# ST_LINK_V3EC.net
KiCad netlist of a schematic drawn in Altium Designer
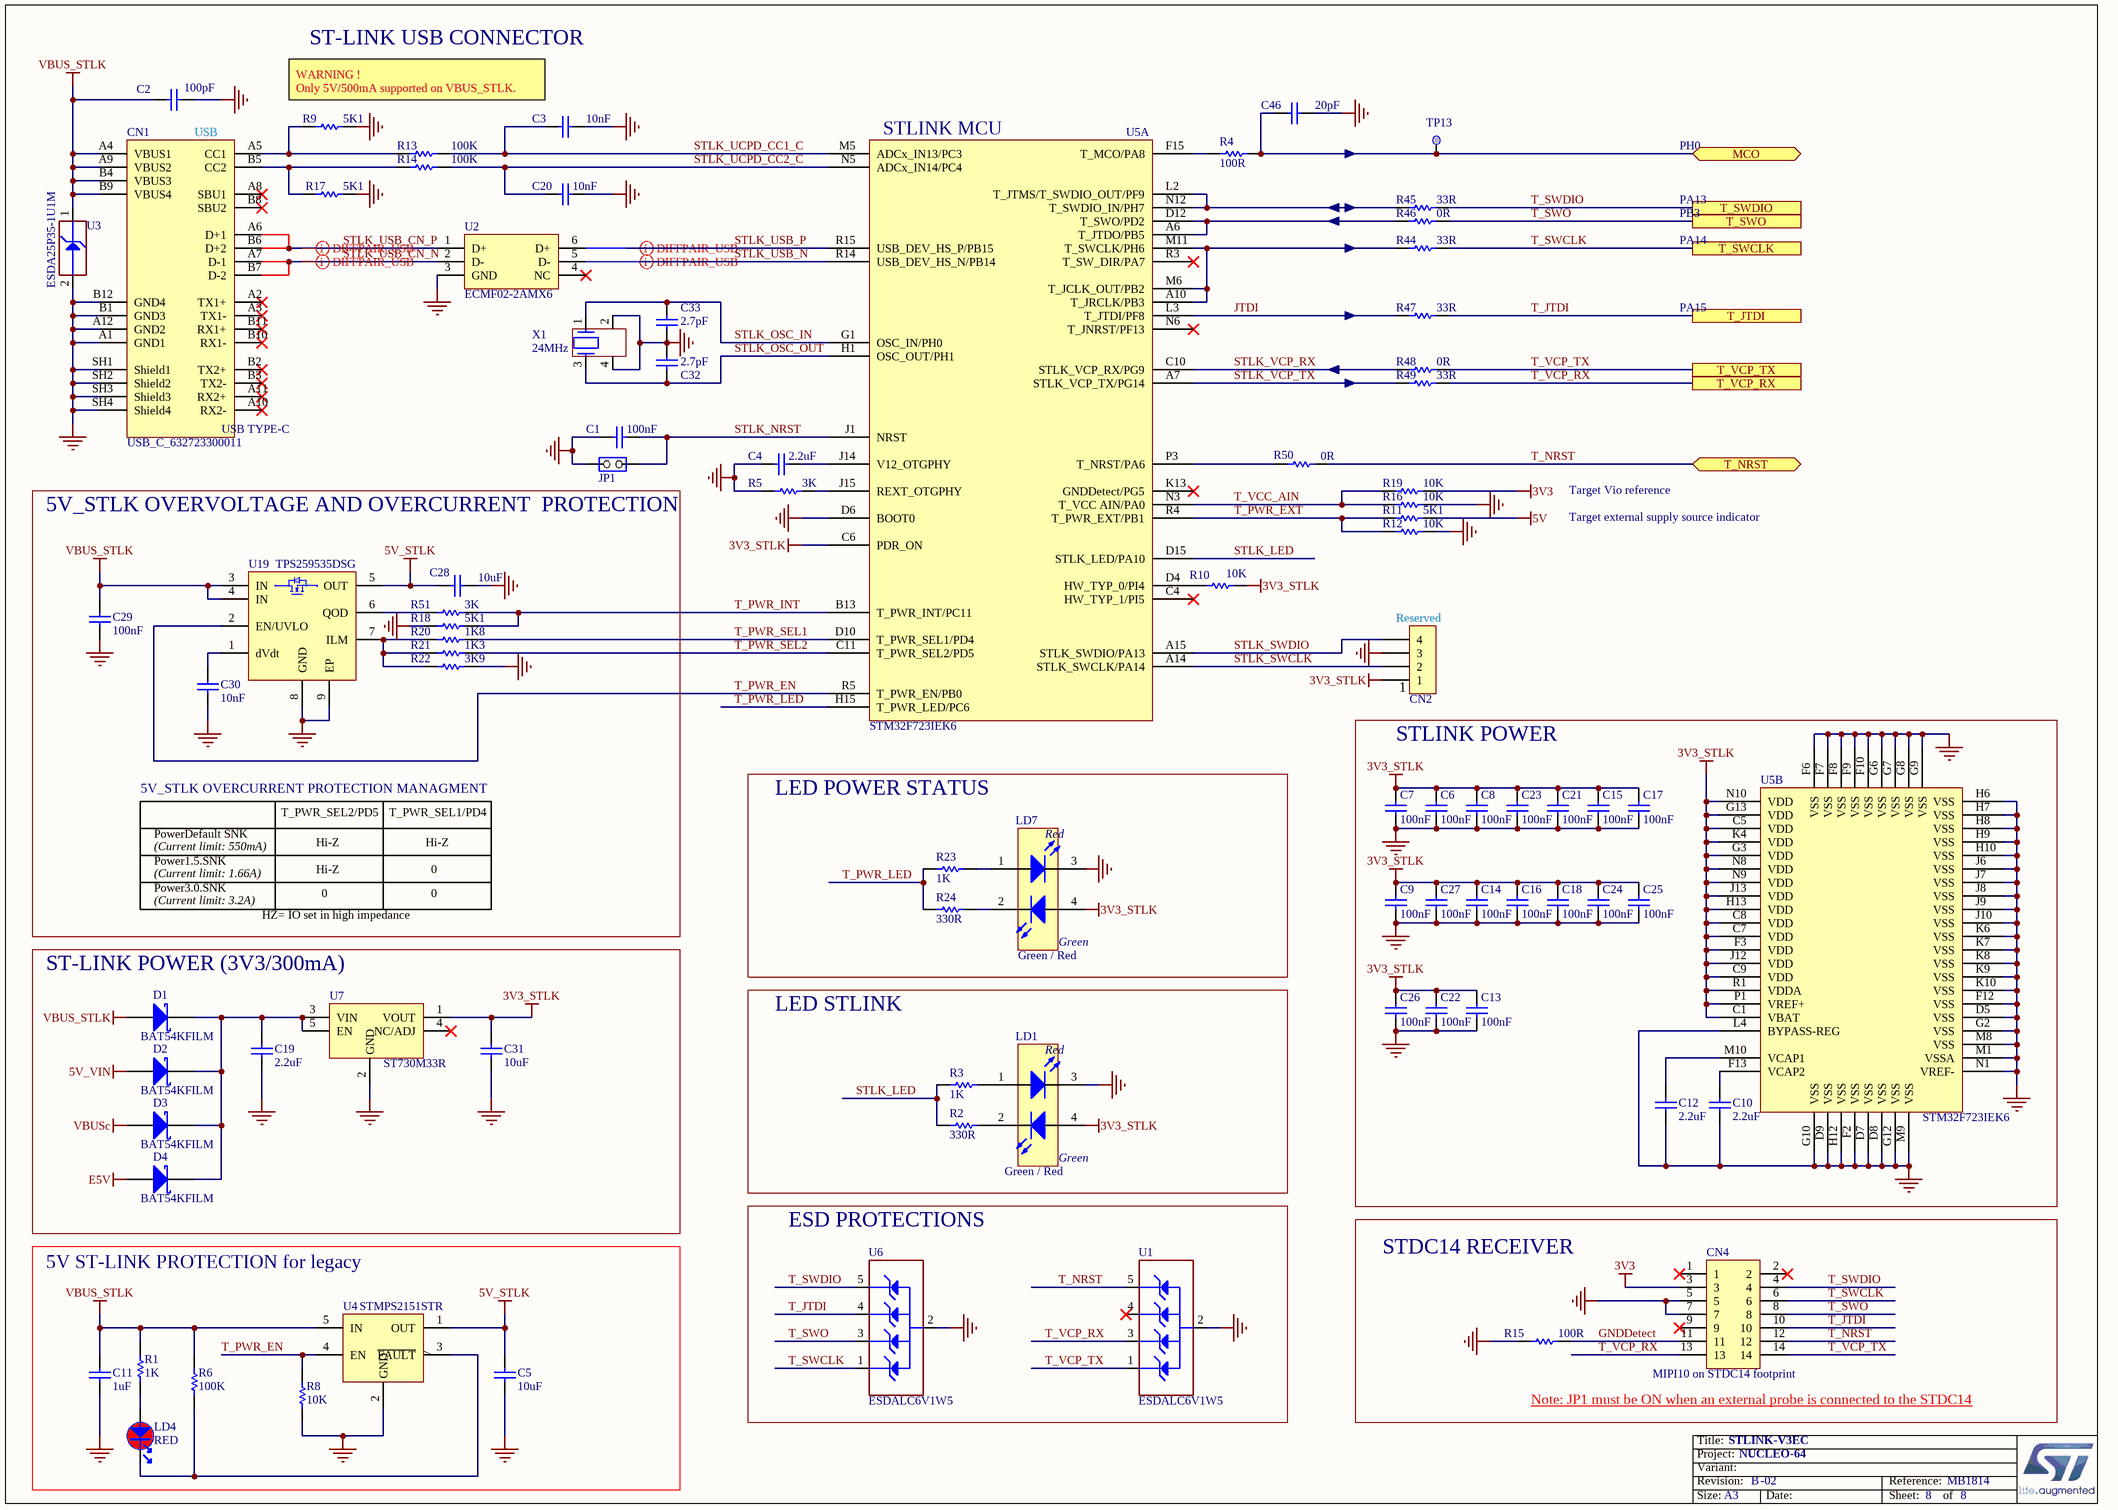
[diagram p0: ST_LINK_V3EC.SchDoc]

(export (version "E")
  (design (tool "Eeschema 10.0.6"))
  (components
    (comp (ref "C1")
      (value "100nF")
      (footprint "C0402")
      (description "Capacitor, MLCC, 100nF, 16V, X7R, 10%, 0402, T=0.5mm")
      (fields
        (field (name "INTERNAL_PART_NUMBER") "MCD-00006")
        (field (name "MANUFACTURER_PART_NUMBER") "CC0402KRX7R7BB104")
        (field (name "PROVIDED_BY") "SUBCO")
      )
      (libsource (lib "MCD_PARTS_database") (part "Capacitor"))
    )
    (comp (ref "C2")
      (value "100pF")
      (footprint "C0402")
      (description "Capacitor, MLCC, 100pF, 50V, NPO, +/-5%, 0402, T=0.5mm")
      (fields (field (name "INTERNAL_PART_NUMBER") "MCD-00205") (field (name "MANUFACTURER") "YAGEO"))
      (libsource (lib "MCD_PARTS_database") (part "Capacitor"))
    )
    (comp (ref "C3")
      (value "10nF")
      (footprint "C0402")
      (description "Capacitor, MLCC, 10nF, 50V, X7R, +/-10%, 0402, T=0.5mm")
      (fields (field (name "INTERNAL_PART_NUMBER") "MCD-02198") (field (name "MANUFACTURER") "YAGEO"))
      (libsource (lib "MCD_PARTS_database") (part "Capacitor"))
    )
    (comp (ref "C4")
      (value "2.2uF")
      (footprint "C0402")
      (description "Capacitor, MLCC, 2.2uF, 6.3V, X5R, +/-10%, 0402, T=0.5mm")
      (fields (field (name "INTERNAL_PART_NUMBER") "MCD-02606") (field (name "MANUFACTURER") "YAGEO"))
      (libsource (lib "MCD_PARTS_database") (part "Capacitor"))
    )
    (comp (ref "C5")
      (value "10uF")
      (footprint "C0603")
      (description "Capacitor, MLCC, 10uF, 10V, X5R, +/-10%, 0603, T=0.8mm")
      (fields (field (name "INTERNAL_PART_NUMBER") "MCD-00099") (field (name "MANUFACTURER") "MURATA"))
      (libsource (lib "MCD_PARTS_database") (part "Capacitor"))
    )
    (comp (ref "C6")
      (value "100nF")
      (footprint "C0402")
      (description "Capacitor, MLCC, 100nF, 16V, X7R, 10%, 0402, T=0.5mm")
      (fields
        (field (name "INTERNAL_PART_NUMBER") "MCD-00006")
        (field (name "MANUFACTURER_PART_NUMBER") "CC0402KRX7R7BB104")
        (field (name "PROVIDED_BY") "SUBCO")
      )
      (libsource (lib "MCD_PARTS_database") (part "Capacitor"))
    )
    (comp (ref "C7")
      (value "100nF")
      (footprint "C0402")
      (description "Capacitor, MLCC, 100nF, 16V, X7R, 10%, 0402, T=0.5mm")
      (fields
        (field (name "INTERNAL_PART_NUMBER") "MCD-00006")
        (field (name "MANUFACTURER_PART_NUMBER") "CC0402KRX7R7BB104")
        (field (name "PROVIDED_BY") "SUBCO")
      )
      (libsource (lib "MCD_PARTS_database") (part "Capacitor"))
    )
    (comp (ref "C8")
      (value "100nF")
      (footprint "C0402")
      (description "Capacitor, MLCC, 100nF, 16V, X7R, 10%, 0402, T=0.5mm")
      (fields
        (field (name "INTERNAL_PART_NUMBER") "MCD-00006")
        (field (name "MANUFACTURER_PART_NUMBER") "CC0402KRX7R7BB104")
        (field (name "PROVIDED_BY") "SUBCO")
      )
      (libsource (lib "MCD_PARTS_database") (part "Capacitor"))
    )
    (comp (ref "C9")
      (value "100nF")
      (footprint "C0402")
      (description "Capacitor, MLCC, 100nF, 16V, X7R, 10%, 0402, T=0.5mm")
      (fields
        (field (name "INTERNAL_PART_NUMBER") "MCD-00006")
        (field (name "MANUFACTURER_PART_NUMBER") "CC0402KRX7R7BB104")
        (field (name "PROVIDED_BY") "SUBCO")
      )
      (libsource (lib "MCD_PARTS_database") (part "Capacitor"))
    )
    (comp (ref "C10")
      (value "2.2uF")
      (footprint "C0402")
      (description "Capacitor, MLCC, 2.2uF, 6.3V, X5R, +/-10%, 0402, T=0.5mm")
      (fields (field (name "INTERNAL_PART_NUMBER") "MCD-02606") (field (name "MANUFACTURER") "YAGEO"))
      (libsource (lib "MCD_PARTS_database") (part "Capacitor"))
    )
    (comp (ref "C11")
      (value "1uF")
      (footprint "C0603")
      (description "Capacitor, MLCC, 1uF, 16V, X5R, 10%, 0603, T=0,8mm")
      (fields
        (field (name "INTERNAL_PART_NUMBER") "MCD-00010")
        (field (name "MANUFACTURER_PART_NUMBER") "CC0603KRX5R7BB105")
        (field (name "PROVIDED_BY") "SUBCO")
      )
      (libsource (lib "MCD_PARTS_database") (part "Capacitor"))
    )
    (comp (ref "C12")
      (value "2.2uF")
      (footprint "C0402")
      (description "Capacitor, MLCC, 2.2uF, 6.3V, X5R, +/-10%, 0402, T=0.5mm")
      (fields (field (name "INTERNAL_PART_NUMBER") "MCD-02606") (field (name "MANUFACTURER") "YAGEO"))
      (libsource (lib "MCD_PARTS_database") (part "Capacitor"))
    )
    (comp (ref "C13")
      (value "100nF")
      (footprint "C0402")
      (description "Capacitor, MLCC, 100nF, 16V, X7R, 10%, 0402, T=0.5mm")
      (fields
        (field (name "INTERNAL_PART_NUMBER") "MCD-00006")
        (field (name "MANUFACTURER_PART_NUMBER") "CC0402KRX7R7BB104")
        (field (name "PROVIDED_BY") "SUBCO")
      )
      (libsource (lib "MCD_PARTS_database") (part "Capacitor"))
    )
    (comp (ref "C14")
      (value "100nF")
      (footprint "C0402")
      (description "Capacitor, MLCC, 100nF, 16V, X7R, 10%, 0402, T=0.5mm")
      (fields
        (field (name "INTERNAL_PART_NUMBER") "MCD-00006")
        (field (name "MANUFACTURER_PART_NUMBER") "CC0402KRX7R7BB104")
        (field (name "PROVIDED_BY") "SUBCO")
      )
      (libsource (lib "MCD_PARTS_database") (part "Capacitor"))
    )
    (comp (ref "C15")
      (value "100nF")
      (footprint "C0402")
      (description "Capacitor, MLCC, 100nF, 16V, X7R, 10%, 0402, T=0.5mm")
      (fields
        (field (name "INTERNAL_PART_NUMBER") "MCD-00006")
        (field (name "MANUFACTURER_PART_NUMBER") "CC0402KRX7R7BB104")
        (field (name "PROVIDED_BY") "SUBCO")
      )
      (libsource (lib "MCD_PARTS_database") (part "Capacitor"))
    )
    (comp (ref "C16")
      (value "100nF")
      (footprint "C0402")
      (description "Capacitor, MLCC, 100nF, 16V, X7R, 10%, 0402, T=0.5mm")
      (fields
        (field (name "INTERNAL_PART_NUMBER") "MCD-00006")
        (field (name "MANUFACTURER_PART_NUMBER") "CC0402KRX7R7BB104")
        (field (name "PROVIDED_BY") "SUBCO")
      )
      (libsource (lib "MCD_PARTS_database") (part "Capacitor"))
    )
    (comp (ref "C17")
      (value "100nF")
      (footprint "C0402")
      (description "Capacitor, MLCC, 100nF, 16V, X7R, 10%, 0402, T=0.5mm")
      (fields
        (field (name "INTERNAL_PART_NUMBER") "MCD-00006")
        (field (name "MANUFACTURER_PART_NUMBER") "CC0402KRX7R7BB104")
        (field (name "PROVIDED_BY") "SUBCO")
      )
      (libsource (lib "MCD_PARTS_database") (part "Capacitor"))
    )
    (comp (ref "C18")
      (value "100nF")
      (footprint "C0402")
      (description "Capacitor, MLCC, 100nF, 16V, X7R, 10%, 0402, T=0.5mm")
      (fields
        (field (name "INTERNAL_PART_NUMBER") "MCD-00006")
        (field (name "MANUFACTURER_PART_NUMBER") "CC0402KRX7R7BB104")
        (field (name "PROVIDED_BY") "SUBCO")
      )
      (libsource (lib "MCD_PARTS_database") (part "Capacitor"))
    )
    (comp (ref "C19")
      (value "2.2uF")
      (footprint "C0805")
      (description "Capacitor, MLCC, 2.2uF, 25V, X7R, +/-10%, 0805, T=1,25mm")
      (fields
        (field (name "INTERNAL_PART_NUMBER") "MCD-02372")
        (field (name "MANUFACTURER_PART_NUMBER") "GRM21BR71E225KE11L")
        (field (name "PROVIDED_BY") "SUBCO")
      )
      (libsource (lib "MCD_PARTS_database") (part "Capacitor"))
    )
    (comp (ref "C20")
      (value "10nF")
      (footprint "C0402")
      (description "Capacitor, MLCC, 10nF, 50V, X7R, +/-10%, 0402, T=0.5mm")
      (fields (field (name "INTERNAL_PART_NUMBER") "MCD-02198") (field (name "MANUFACTURER") "YAGEO"))
      (libsource (lib "MCD_PARTS_database") (part "Capacitor"))
    )
    (comp (ref "C21")
      (value "100nF")
      (footprint "C0402")
      (description "Capacitor, MLCC, 100nF, 16V, X7R, 10%, 0402, T=0.5mm")
      (fields
        (field (name "INTERNAL_PART_NUMBER") "MCD-00006")
        (field (name "MANUFACTURER_PART_NUMBER") "CC0402KRX7R7BB104")
        (field (name "PROVIDED_BY") "SUBCO")
      )
      (libsource (lib "MCD_PARTS_database") (part "Capacitor"))
    )
    (comp (ref "C22")
      (value "100nF")
      (footprint "C0402")
      (description "Capacitor, MLCC, 100nF, 16V, X7R, 10%, 0402, T=0.5mm")
      (fields
        (field (name "INTERNAL_PART_NUMBER") "MCD-00006")
        (field (name "MANUFACTURER_PART_NUMBER") "CC0402KRX7R7BB104")
        (field (name "PROVIDED_BY") "SUBCO")
      )
      (libsource (lib "MCD_PARTS_database") (part "Capacitor"))
    )
    (comp (ref "C23")
      (value "100nF")
      (footprint "C0402")
      (description "Capacitor, MLCC, 100nF, 16V, X7R, 10%, 0402, T=0.5mm")
      (fields
        (field (name "INTERNAL_PART_NUMBER") "MCD-00006")
        (field (name "MANUFACTURER_PART_NUMBER") "CC0402KRX7R7BB104")
        (field (name "PROVIDED_BY") "SUBCO")
      )
      (libsource (lib "MCD_PARTS_database") (part "Capacitor"))
    )
    (comp (ref "C24")
      (value "100nF")
      (footprint "C0402")
      (description "Capacitor, MLCC, 100nF, 16V, X7R, 10%, 0402, T=0.5mm")
      (fields
        (field (name "INTERNAL_PART_NUMBER") "MCD-00006")
        (field (name "MANUFACTURER_PART_NUMBER") "CC0402KRX7R7BB104")
        (field (name "PROVIDED_BY") "SUBCO")
      )
      (libsource (lib "MCD_PARTS_database") (part "Capacitor"))
    )
    (comp (ref "C25")
      (value "100nF")
      (footprint "C0402")
      (description "Capacitor, MLCC, 100nF, 16V, X7R, 10%, 0402, T=0.5mm")
      (fields
        (field (name "INTERNAL_PART_NUMBER") "MCD-00006")
        (field (name "MANUFACTURER_PART_NUMBER") "CC0402KRX7R7BB104")
        (field (name "PROVIDED_BY") "SUBCO")
      )
      (libsource (lib "MCD_PARTS_database") (part "Capacitor"))
    )
    (comp (ref "C26")
      (value "100nF")
      (footprint "C0402")
      (description "Capacitor, MLCC, 100nF, 16V, X7R, 10%, 0402, T=0.5mm")
      (fields
        (field (name "INTERNAL_PART_NUMBER") "MCD-00006")
        (field (name "MANUFACTURER_PART_NUMBER") "CC0402KRX7R7BB104")
        (field (name "PROVIDED_BY") "SUBCO")
      )
      (libsource (lib "MCD_PARTS_database") (part "Capacitor"))
    )
    (comp (ref "C27")
      (value "100nF")
      (footprint "C0402")
      (description "Capacitor, MLCC, 100nF, 16V, X7R, 10%, 0402, T=0.5mm")
      (fields
        (field (name "INTERNAL_PART_NUMBER") "MCD-00006")
        (field (name "MANUFACTURER_PART_NUMBER") "CC0402KRX7R7BB104")
        (field (name "PROVIDED_BY") "SUBCO")
      )
      (libsource (lib "MCD_PARTS_database") (part "Capacitor"))
    )
    (comp (ref "C28")
      (value "10uF")
      (footprint "C0603")
      (description "Capacitor, MLCC, 10uF, 10V, X5R, +/-10%, 0603, T=0.8mm")
      (fields (field (name "INTERNAL_PART_NUMBER") "MCD-00099") (field (name "MANUFACTURER") "MURATA"))
      (libsource (lib "MCD_PARTS_database") (part "Capacitor"))
    )
    (comp (ref "C29")
      (value "100nF")
      (footprint "C0402")
      (description "Capacitor, MLCC, 100nF, 25V, X7R, +/-10%, 0402, T=0.5mm")
      (fields (field (name "INTERNAL_PART_NUMBER") "MCD-02355") (field (name "MANUFACTURER") "WALSIN"))
      (libsource (lib "MCD_PARTS_database") (part "Capacitor"))
    )
    (comp (ref "C30")
      (value "10nF")
      (footprint "C0402")
      (description "Capacitor, MLCC, 10nF, 50V, X7R, +/-10%, 0402, T=0.5mm")
      (fields (field (name "INTERNAL_PART_NUMBER") "MCD-02198") (field (name "MANUFACTURER") "YAGEO"))
      (libsource (lib "MCD_PARTS_database") (part "Capacitor"))
    )
    (comp (ref "C31")
      (value "10uF")
      (footprint "C0603")
      (description "Capacitor, MLCC, 10uF, 10V, X5R, +/-10%, 0603, T=0.8mm")
      (fields (field (name "INTERNAL_PART_NUMBER") "MCD-00099") (field (name "MANUFACTURER") "MURATA"))
      (libsource (lib "MCD_PARTS_database") (part "Capacitor"))
    )
    (comp (ref "C32")
      (value "2.7pF")
      (footprint "C0402")
      (description "Capacitor, MLCC, 2.7pF, 50V, NPO, +/-0.1pF, 0402, T=0.5mm")
      (fields (field (name "INTERNAL_PART_NUMBER") "MCD-01774") (field (name "MANUFACTURER") "YAGEO"))
      (libsource (lib "MCD_PARTS_database") (part "Capacitor"))
    )
    (comp (ref "C33")
      (value "2.7pF")
      (footprint "C0402")
      (description "Capacitor, MLCC, 2.7pF, 50V, NPO, +/-0.1pF, 0402, T=0.5mm")
      (fields (field (name "INTERNAL_PART_NUMBER") "MCD-01774") (field (name "MANUFACTURER") "YAGEO"))
      (libsource (lib "MCD_PARTS_database") (part "Capacitor"))
    )
    (comp (ref "C46")
      (value "20pF")
      (footprint "C0402")
      (description "Capacitor, MLCC, 20pF, 50V, NPO, +/- 5%, 0402, T=0.5mm")
      (fields (field (name "INTERNAL_PART_NUMBER") "MCD-00016") (field (name "MANUFACTURER") "YAGEO"))
      (libsource (lib "MCD_PARTS_database") (part "Capacitor"))
    )
    (comp (ref "CN1")
      (value "USB_C_632723300011")
      (footprint "CON_USB-TYPEC_WE_632723300011")
      (description "USB_TypeC, 24pins, RA, TH, T=1.9mm (USB certified)")
      (fields
        (field (name "INTERNAL_PART_NUMBER") "MCD-02273")
        (field (name "MANUFACTURER") "WURTH ELEKTRONIK")
      )
      (libsource (lib "MCD_PARTS_database") (part "USB_TYPE_C_Receptacle"))
    )
    (comp (ref "CN2")
      (value "Header 4x1")
      (footprint "CON_SAMTEC_TSW-104-07-G-S")
      (description "Header, 4x1, 2,54mm, VR, TH, Height 5.84mm/2.54mm")
      (fields
        (field (name "INTERNAL_PART_NUMBER") "MCD-00029")
        (field (name "MANUFACTURER_PART_NUMBER") "TSW-104-07-x-S")
        (field (name "PROVIDED_BY") "SUBCO")
      )
      (libsource (lib "MCD_PARTS_database") (part "Header 4x1"))
    )
    (comp (ref "CN4")
      (value "Header 7x2")
      (footprint "CON_STDC14_Receiver_MEDIUM_WITH_MIPI10_3D")
      (description "Header, 5x2, 1.27mm, VR, SMD, T=5.97mm/3.05mm")
      (fields (field (name "INTERNAL_PART_NUMBER") "MCD-01226") (field (name "MANUFACTURER") "SAMTEC"))
      (libsource (lib "MCD_PARTS_database") (part "Header 7x2"))
    )
    (comp (ref "D1")
      (value "BAT54KFILM")
      (footprint "DIO_SOD523_1A_2K")
      (description "Small signal Schottky diodes")
      (fields (field (name "INTERNAL_PART_NUMBER") "MCD-01677") (field (name "BMS_PART_NUMBER") "9151123"))
      (libsource (lib "MCD_PARTS_database") (part "SCHOTTKY_1A_2K"))
    )
    (comp (ref "D2")
      (value "BAT54KFILM")
      (footprint "DIO_SOD523_1A_2K")
      (description "Small signal Schottky diodes")
      (fields (field (name "INTERNAL_PART_NUMBER") "MCD-01677") (field (name "BMS_PART_NUMBER") "9151123"))
      (libsource (lib "MCD_PARTS_database") (part "SCHOTTKY_1A_2K"))
    )
    (comp (ref "D3")
      (value "BAT54KFILM")
      (footprint "DIO_SOD523_1A_2K")
      (description "Small signal Schottky diodes")
      (fields (field (name "INTERNAL_PART_NUMBER") "MCD-01677") (field (name "BMS_PART_NUMBER") "9151123"))
      (libsource (lib "MCD_PARTS_database") (part "SCHOTTKY_1A_2K"))
    )
    (comp (ref "D4")
      (value "BAT54KFILM")
      (footprint "DIO_SOD523_1A_2K")
      (description "Small signal Schottky diodes")
      (fields (field (name "INTERNAL_PART_NUMBER") "MCD-01677") (field (name "BMS_PART_NUMBER") "9151123"))
      (libsource (lib "MCD_PARTS_database") (part "SCHOTTKY_1A_2K"))
    )
    (comp (ref "JP1")
      (value "Jumper_Header 2x1")
      (footprint "CON_SAMTEC_TSW-102-07-G-S")
      (description "Header, 2x1, 2,54mm, VR, TH, Height 5.84mm/2.54mm")
      (fields (field (name "INTERNAL_PART_NUMBER") "MCD-00045") (field (name "MANUFACTURER") "SAMTEC"))
      (libsource (lib "MCD_PARTS_database") (part "Jumper_Header 2x1"))
    )
    (comp (ref "LD1")
      (value "Green / Red")
      (footprint "LED_BI-GR_WE-150141SV73110")
      (description "LED Bicolor, Green/Red, 2V, 20mA,  4-PLCC")
      (fields
        (field (name "INTERNAL_PART_NUMBER") "MCD-02631")
        (field (name "MANUFACTURER") "WURTH ELEKTRONIK")
      )
      (libsource (lib "MCD_PARTS_database") (part "LED_BICOLOR"))
    )
    (comp (ref "LD4")
      (value "RED")
      (footprint "LED_0603_VISHAY_VLMS1300-GS08_RED_1A2K_H0P8")
      (description "LED Red, 0603 SMD, 2V Forward Voltage")
      (fields
        (field (name "INTERNAL_PART_NUMBER") "MCD-00587")
        (field (name "MANUFACTURER_PART_NUMBER") "VLMS1300-GS08")
        (field (name "PROVIDED_BY") "SUBCO")
      )
      (libsource (lib "MCD_PARTS_database") (part "LED_red"))
    )
    (comp (ref "LD7")
      (value "Green / Red")
      (footprint "LED_BI-GR_WE-150141SV73110")
      (description "LED Bicolor, Green/Red, 2V, 20mA,  4-PLCC")
      (fields
        (field (name "INTERNAL_PART_NUMBER") "MCD-02631")
        (field (name "MANUFACTURER") "WURTH ELEKTRONIK")
      )
      (libsource (lib "MCD_PARTS_database") (part "LED_BICOLOR"))
    )
    (comp (ref "R1")
      (value "1K")
      (footprint "R0402")
      (description "Resistor,1K,0402,1%,1/16W")
      (fields
        (field (name "INTERNAL_PART_NUMBER") "MCD-00061")
        (field (name "MANUFACTURER_PART_NUMBER") "RC0402FR-071KL")
        (field (name "PROVIDED_BY") "SUBCO")
      )
      (libsource (lib "MCD_PARTS_database") (part "Resistor"))
    )
    (comp (ref "R2")
      (value "330R")
      (footprint "R0402")
      (description "Resistor, 330R, 0402, +/-1%, 1/16W")
      (fields (field (name "INTERNAL_PART_NUMBER") "MCD-00062") (field (name "MANUFACTURER") "YAGEO"))
      (libsource (lib "MCD_PARTS_database") (part "Resistor"))
    )
    (comp (ref "R3")
      (value "1K")
      (footprint "R0402")
      (description "Resistor, 1K, 0402, +/-0.1%, 1/16W, +/-25ppm/°C")
      (fields (field (name "INTERNAL_PART_NUMBER") "MCD-02665") (field (name "MANUFACTURER") "YAGEO"))
      (libsource (lib "MCD_PARTS_database") (part "Resistor"))
    )
    (comp (ref "R4")
      (value "100R")
      (footprint "R0402")
      (description "Resistor, 100R, 0402, +/-1%, 1/16W")
      (fields (field (name "INTERNAL_PART_NUMBER") "MCD-00119") (field (name "MANUFACTURER") "YAGEO"))
      (libsource (lib "MCD_PARTS_database") (part "Resistor"))
    )
    (comp (ref "R5")
      (value "3K")
      (footprint "R0402")
      (description "Resistor,3K,0402,1%,1/16W")
      (fields
        (field (name "INTERNAL_PART_NUMBER") "MCD-00185")
        (field (name "MANUFACTURER_PART_NUMBER") "RC0402FR-073KL")
        (field (name "PROVIDED_BY") "SUBCO")
      )
      (libsource (lib "MCD_PARTS_database") (part "Resistor"))
    )
    (comp (ref "R6")
      (value "100K")
      (footprint "R0402")
      (description "Resistor,100K,0402,1%,1/16W")
      (fields
        (field (name "INTERNAL_PART_NUMBER") "MCD-00059")
        (field (name "MANUFACTURER_PART_NUMBER") "RC0402FR-07100KL")
        (field (name "PROVIDED_BY") "SUBCO")
      )
      (libsource (lib "MCD_PARTS_database") (part "Resistor"))
    )
    (comp (ref "R8")
      (value "10K")
      (footprint "R0402")
      (description "Resistor,10K,0402,1%,1/16W")
      (fields
        (field (name "INTERNAL_PART_NUMBER") "MCD-00053")
        (field (name "MANUFACTURER_PART_NUMBER") "RC0402FR-0710KL")
        (field (name "PROVIDED_BY") "SUBCO")
      )
      (libsource (lib "MCD_PARTS_database") (part "Resistor"))
    )
    (comp (ref "R9")
      (value "5K1")
      (footprint "R0402")
      (description "Resistor, 5K1, 0402, +/-1%, 1/16W")
      (fields (field (name "INTERNAL_PART_NUMBER") "MCD-00333") (field (name "MANUFACTURER") "YAGEO"))
      (libsource (lib "MCD_PARTS_database") (part "Resistor"))
    )
    (comp (ref "R10")
      (value "10K")
      (footprint "R0402")
      (description "Resistor,10K,0402,1%,1/16W")
      (fields
        (field (name "INTERNAL_PART_NUMBER") "MCD-00053")
        (field (name "MANUFACTURER_PART_NUMBER") "RC0402FR-0710KL")
        (field (name "PROVIDED_BY") "SUBCO")
      )
      (libsource (lib "MCD_PARTS_database") (part "Resistor"))
    )
    (comp (ref "R11")
      (value "5K1")
      (footprint "R0402")
      (description "Resistor, 5K1, 0402, +/-1%, 1/16W")
      (fields (field (name "INTERNAL_PART_NUMBER") "MCD-00333") (field (name "MANUFACTURER") "YAGEO"))
      (libsource (lib "MCD_PARTS_database") (part "Resistor"))
    )
    (comp (ref "R12")
      (value "10K")
      (footprint "R0402")
      (description "Resistor, 10K, 0402, +/-1%, 1/16W")
      (fields (field (name "INTERNAL_PART_NUMBER") "MCD-00053") (field (name "BMS_PART_NUMBER") "9131590"))
      (libsource (lib "MCD_PARTS_database") (part "Resistor"))
    )
    (comp (ref "R13")
      (value "100K")
      (footprint "R0402")
      (description "Resistor, 100K, 0402, +/-1%, 1/16W")
      (fields (field (name "INTERNAL_PART_NUMBER") "MCD-00059") (field (name "MANUFACTURER") "YAGEO"))
      (libsource (lib "MCD_PARTS_database") (part "Resistor"))
    )
    (comp (ref "R14")
      (value "100K")
      (footprint "R0402")
      (description "Resistor, 100K, 0402, +/-1%, 1/16W")
      (fields (field (name "INTERNAL_PART_NUMBER") "MCD-00059") (field (name "MANUFACTURER") "YAGEO"))
      (libsource (lib "MCD_PARTS_database") (part "Resistor"))
    )
    (comp (ref "R15")
      (value "100R")
      (footprint "R0402")
      (description "Resistor, 100R, 0402, +/-1%, 1/16W")
      (fields (field (name "INTERNAL_PART_NUMBER") "MCD-00119") (field (name "MANUFACTURER") "YAGEO"))
      (libsource (lib "MCD_PARTS_database") (part "Resistor"))
    )
    (comp (ref "R16")
      (value "10K")
      (footprint "R0402")
      (description "Resistor, 10K, 0402, +/-1%, 1/16W")
      (fields (field (name "INTERNAL_PART_NUMBER") "MCD-00053") (field (name "BMS_PART_NUMBER") "9131590"))
      (libsource (lib "MCD_PARTS_database") (part "Resistor"))
    )
    (comp (ref "R17")
      (value "5K1")
      (footprint "R0402")
      (description "Resistor, 5K1, 0402, +/-1%, 1/16W")
      (fields (field (name "INTERNAL_PART_NUMBER") "MCD-00333") (field (name "MANUFACTURER") "YAGEO"))
      (libsource (lib "MCD_PARTS_database") (part "Resistor"))
    )
    (comp (ref "R18")
      (value "5K1")
      (footprint "R0402")
      (description "Resistor, 5K1, 0402, +/-1%, 1/16W")
      (fields (field (name "INTERNAL_PART_NUMBER") "MCD-00333") (field (name "MANUFACTURER") "YAGEO"))
      (libsource (lib "MCD_PARTS_database") (part "Resistor"))
    )
    (comp (ref "R19")
      (value "10K")
      (footprint "R0402")
      (description "Resistor, 10K, 0402, +/-1%, 1/16W")
      (fields (field (name "INTERNAL_PART_NUMBER") "MCD-00053") (field (name "BMS_PART_NUMBER") "9131590"))
      (libsource (lib "MCD_PARTS_database") (part "Resistor"))
    )
    (comp (ref "R20")
      (value "1K8")
      (footprint "R0402")
      (description "Resistor, 1K8, 0402, +/-1%, 1/16W")
      (fields (field (name "INTERNAL_PART_NUMBER") "MCD-00409") (field (name "MANUFACTURER") "YAGEO"))
      (libsource (lib "MCD_PARTS_database") (part "Resistor"))
    )
    (comp (ref "R21")
      (value "1K3")
      (footprint "R0402")
      (description "Resistor, 1K3, 0402, +/-1%, 1/16W")
      (fields (field (name "INTERNAL_PART_NUMBER") "MCD-00381") (field (name "MANUFACTURER") "YAGEO"))
      (libsource (lib "MCD_PARTS_database") (part "Resistor"))
    )
    (comp (ref "R22")
      (value "3K9")
      (footprint "R0402")
      (description "Resistor, 3K9, 0402, +/-1%, 1/16W, +/-100ppm/°C")
      (fields (field (name "INTERNAL_PART_NUMBER") "MCD-02455") (field (name "MANUFACTURER") "YAGEO"))
      (libsource (lib "MCD_PARTS_database") (part "Resistor"))
    )
    (comp (ref "R23")
      (value "1K")
      (footprint "R0402")
      (description "Resistor, 1K, 0402, +/-0.1%, 1/16W, +/-25ppm/°C")
      (fields (field (name "INTERNAL_PART_NUMBER") "MCD-02665") (field (name "MANUFACTURER") "YAGEO"))
      (libsource (lib "MCD_PARTS_database") (part "Resistor"))
    )
    (comp (ref "R24")
      (value "330R")
      (footprint "R0402")
      (description "Resistor, 330R, 0402, +/-1%, 1/16W")
      (fields (field (name "INTERNAL_PART_NUMBER") "MCD-00062") (field (name "MANUFACTURER") "YAGEO"))
      (libsource (lib "MCD_PARTS_database") (part "Resistor"))
    )
    (comp (ref "R44")
      (value "33R")
      (footprint "R0402")
      (description "Resistor, 33R, 0402, +/-1%, 1/16W")
      (fields (field (name "INTERNAL_PART_NUMBER") "MCD-00455") (field (name "MANUFACTURER") "YAGEO"))
      (libsource (lib "MCD_PARTS_database") (part "Resistor"))
    )
    (comp (ref "R45")
      (value "33R")
      (footprint "R0402")
      (description "Resistor, 33R, 0402, +/-1%, 1/16W")
      (fields (field (name "INTERNAL_PART_NUMBER") "MCD-00455") (field (name "MANUFACTURER") "YAGEO"))
      (libsource (lib "MCD_PARTS_database") (part "Resistor"))
    )
    (comp (ref "R46")
      (value "0R")
      (footprint "R0402")
      (description "Resistor, 0R, 0402, +/-5%, 1/16W")
      (fields (field (name "INTERNAL_PART_NUMBER") "MCD-00052") (field (name "MANUFACTURER") "YAGEO"))
      (libsource (lib "MCD_PARTS_database") (part "Resistor"))
    )
    (comp (ref "R47")
      (value "33R")
      (footprint "R0402")
      (description "Resistor, 33R, 0402, +/-1%, 1/16W")
      (fields (field (name "INTERNAL_PART_NUMBER") "MCD-00455") (field (name "MANUFACTURER") "YAGEO"))
      (libsource (lib "MCD_PARTS_database") (part "Resistor"))
    )
    (comp (ref "R48")
      (value "0R")
      (footprint "R0402")
      (description "Resistor, 0R, 0402, +/-5%, 1/16W")
      (fields (field (name "INTERNAL_PART_NUMBER") "MCD-00052") (field (name "MANUFACTURER") "YAGEO"))
      (libsource (lib "MCD_PARTS_database") (part "Resistor"))
    )
    (comp (ref "R49")
      (value "33R")
      (footprint "R0402")
      (description "Resistor, 33R, 0402, +/-1%, 1/16W")
      (fields (field (name "INTERNAL_PART_NUMBER") "MCD-00455") (field (name "MANUFACTURER") "YAGEO"))
      (libsource (lib "MCD_PARTS_database") (part "Resistor"))
    )
    (comp (ref "R50")
      (value "0R")
      (footprint "R0402")
      (description "Resistor, 0R, 0402, +/-5%, 1/16W")
      (fields (field (name "INTERNAL_PART_NUMBER") "MCD-00052") (field (name "MANUFACTURER") "YAGEO"))
      (libsource (lib "MCD_PARTS_database") (part "Resistor"))
    )
    (comp (ref "R51")
      (value "3K")
      (footprint "R0402")
      (description "Resistor, 3K, 0402, +/-1%, 1/16W")
      (fields (field (name "INTERNAL_PART_NUMBER") "MCD-00185") (field (name "MANUFACTURER") "YAGEO"))
      (libsource (lib "MCD_PARTS_database") (part "Resistor"))
    )
    (comp (ref "TP13")
      (value "Test Point")
      (footprint "TP_SMD_1MM")
      (description "Test Point 1mm")
      (fields
        (field (name "INTERNAL_PART_NUMBER") "MCD-00074")
        (field (name "MANUFACTURER_PART_NUMBER") "n/a")
      )
      (libsource (lib "MCD_PARTS_database") (part "Test Point"))
    )
    (comp (ref "U1")
      (value "ESDALC6V1W5")
      (footprint "ESD_SOT323-5L")
      (description "Dual Transil array for ESD protection")
      (fields (field (name "INTERNAL_PART_NUMBER") "MCD-00136") (field (name "BMS_PART_NUMBER") "9151112"))
      (libsource (lib "MCD_PARTS_database") (part "ESDALC6V1W5"))
    )
    (comp (ref "U2")
      (value "ECMF02-2AMX6")
      (footprint "ESD_QFN-6L_1P7X1P5_P050")
      (description "Common mode filter with ESD protection for USB 2.0 interface")
      (fields (field (name "INTERNAL_PART_NUMBER") "MCD-00649") (field (name "BMS_PART_NUMBER") "9151138"))
      (libsource (lib "MCD_PARTS_database") (part "ECMF02-2AMX6"))
    )
    (comp (ref "U3")
      (value "ESDA25P35-1U1M")
      (footprint "ESD_QFN1610_2N_1K_2A")
      (description "High power Transient voltage suppressor:25V/35A EOS and ESD transients protection.")
      (fields
        (field (name "INTERNAL_PART_NUMBER") "MCD-01207")
        (field (name "MANUFACTURER") "STMICROELECTRONICS")
        (field (name "PROVIDED_BY") "SUBCO with ST control")
      )
      (libsource (lib "MCD_PARTS_database") (part "ESD-TRANSIL"))
    )
    (comp (ref "U4")
      (value "STMPS2151STR")
      (footprint "MOS_SOT23-5L")
      (description "500mA, Enhanced single channel power switches with active high enable pin")
      (fields
        (field (name "INTERNAL_PART_NUMBER") "MCD-00159")
        (field (name "MANUFACTURER") "STMICROELECTRONICS")
        (field (name "PROVIDED_BY") "Subcon")
      )
      (libsource (lib "MCD_PARTS_database") (part "STMPS2151STR"))
    )
    (comp (ref "U5")
      (value "STM32F723IEK6")
      (footprint "ICC_UFBGA201_176+25_10X10_P065")
      (description "STM32F723IEK  (STM32F7) BGA176")
      (fields (field (name "INTERNAL_PART_NUMBER") "MCD-02706") (field (name "BMS_PART_NUMBER") "9175300"))
      (libsource (lib "MCD_PARTS_database") (part "STLINK-V3EC"))
    )
    (comp (ref "U6")
      (value "ESDALC6V1W5")
      (footprint "ESD_SOT323-5L")
      (description "Dual Transil array for ESD protection")
      (fields (field (name "INTERNAL_PART_NUMBER") "MCD-00136") (field (name "BMS_PART_NUMBER") "9151112"))
      (libsource (lib "MCD_PARTS_database") (part "ESDALC6V1W5"))
    )
    (comp (ref "U7")
      (value "ST730M33R")
      (footprint "ICC_SOT23-5L_H1P45")
      (description "LDO, 3.3V, 300mA, High input voltage: 2.5V to 28V, SOT23-5L")
      (fields
        (field (name "INTERNAL_PART_NUMBER") "MCD-02514")
        (field (name "MANUFACTURER") "STMICROELECTRONICS")
      )
      (libsource (lib "MCD_PARTS_database") (part "ST730M33R"))
    )
    (comp (ref "U19")
      (value "TPS259535DSG")
      (footprint "ICC_WSON8-EPAD_2X2_P050")
      (description "eFuse with Fast Overvoltage Protection 2.7V to 18V 4A 34mOhm 8-Pin WSON")
      (fields
        (field (name "INTERNAL_PART_NUMBER") "MCD-02532")
        (field (name "MANUFACTURER") "TEXAS INSTRUMENTS")
      )
      (libsource (lib "MCD_PARTS_database") (part "TPS259535DSG"))
    )
    (comp (ref "X1")
      (value "24MHz")
      (footprint "CRY_NX2016SA_4P")
      (description "Crystal, 24MHz, 6pF, +/-20ppm, 80R, 2x1.6mm")
      (fields (field (name "INTERNAL_PART_NUMBER") "MCD-01036") (field (name "BMS_PART_NUMBER") "9157045"))
      (libsource (lib "MCD_PARTS_database") (part "XTAL_4_PINS"))
    )
  )
  (nets
    (net (code "1") (name "/GNDDetect") (class "Default")
      (node (ref "CN4") (pin "11") (pinfunction "11_11") (pintype "passive"))
      (node (ref "R15") (pin "2") (pinfunction "2_2") (pintype "passive"))
    )
    (net (code "2") (name "/JTDI") (class "Default")
      (node (ref "R47") (pin "1") (pinfunction "1_1") (pintype "passive"))
      (node (ref "U5") (pin "L3") (pinfunction "T_JTDI/PF8_L3") (pintype "passive"))
    )
    (net (code "3") (name "/MCO") (class "Default")
      (node (ref "C46") (pin "2") (pinfunction "2_2") (pintype "passive"))
      (node (ref "R4") (pin "2") (pinfunction "2_2") (pintype "passive"))
      (node (ref "TP13") (pin "1") (pinfunction "1_1") (pintype "passive"))
    )
    (net (code "4") (name "/STLK_LED") (class "Default")
      (node (ref "R2") (pin "1") (pinfunction "1_1") (pintype "passive"))
      (node (ref "R3") (pin "2") (pinfunction "2_2") (pintype "passive"))
      (node (ref "U5") (pin "D15") (pinfunction "STLK_LED/PA10_D15") (pintype "passive"))
    )
    (net (code "5") (name "/STLK_NRST") (class "Default")
      (node (ref "C1") (pin "2") (pinfunction "2_2") (pintype "passive"))
      (node (ref "JP1") (pin "1") (pinfunction "COMMON_1") (pintype "passive"))
      (node (ref "U5") (pin "J1") (pinfunction "NRST_J1") (pintype "passive"))
    )
    (net (code "6") (name "/STLK_OSC_IN") (class "Default")
      (node (ref "C33") (pin "2") (pinfunction "2_2") (pintype "passive"))
      (node (ref "U5") (pin "G1") (pinfunction "OSC_IN/PH0_G1") (pintype "passive"))
      (node (ref "X1") (pin "1") (pinfunction "1_1") (pintype "passive"))
    )
    (net (code "7") (name "/STLK_OSC_OUT") (class "Default")
      (node (ref "C32") (pin "2") (pinfunction "2_2") (pintype "passive"))
      (node (ref "U5") (pin "H1") (pinfunction "OSC_OUT/PH1_H1") (pintype "passive"))
      (node (ref "X1") (pin "3") (pinfunction "3_3") (pintype "passive"))
    )
    (net (code "8") (name "/STLK_SWCLK") (class "Default")
      (node (ref "CN2") (pin "2") (pinfunction "2_2") (pintype "passive"))
      (node (ref "U5") (pin "A14") (pinfunction "STLK_SWCLK/PA14_A14") (pintype "passive"))
    )
    (net (code "9") (name "/STLK_SWDIO") (class "Default")
      (node (ref "CN2") (pin "4") (pinfunction "4_4") (pintype "passive"))
      (node (ref "U5") (pin "A15") (pinfunction "STLK_SWDIO/PA13_A15") (pintype "passive"))
    )
    (net (code "10") (name "/STLK_UCPD_CC1_C") (class "Default")
      (node (ref "C3") (pin "1") (pinfunction "1_1") (pintype "passive"))
      (node (ref "R13") (pin "2") (pinfunction "2_2") (pintype "passive"))
      (node (ref "U5") (pin "M5") (pinfunction "ADCx_IN13/PC3_M5") (pintype "passive"))
    )
    (net (code "11") (name "/STLK_UCPD_CC2_C") (class "Default")
      (node (ref "C20") (pin "1") (pinfunction "1_1") (pintype "passive"))
      (node (ref "R14") (pin "2") (pinfunction "2_2") (pintype "passive"))
      (node (ref "U5") (pin "N5") (pinfunction "ADCx_IN14/PC4_N5") (pintype "passive"))
    )
    (net (code "12") (name "/STLK_USB_CN_N") (class "Default")
      (node (ref "CN1") (pin "A7") (pinfunction "D-1_A7") (pintype "passive"))
      (node (ref "CN1") (pin "B7") (pinfunction "D-2_B7") (pintype "passive"))
      (node (ref "U2") (pin "2") (pinfunction "D-_2") (pintype "passive"))
    )
    (net (code "13") (name "/STLK_USB_CN_P") (class "Default")
      (node (ref "CN1") (pin "A6") (pinfunction "D+1_A6") (pintype "passive"))
      (node (ref "CN1") (pin "B6") (pinfunction "D+2_B6") (pintype "passive"))
      (node (ref "U2") (pin "1") (pinfunction "D+_1") (pintype "passive"))
    )
    (net (code "14") (name "/STLK_USB_N") (class "Default")
      (node (ref "U2") (pin "5") (pinfunction "D-_5") (pintype "passive"))
      (node (ref "U5") (pin "R14") (pinfunction "USB_DEV_HS_N/PB14_R14") (pintype "passive"))
    )
    (net (code "15") (name "/STLK_USB_P") (class "Default")
      (node (ref "U2") (pin "6") (pinfunction "D+_6") (pintype "passive"))
      (node (ref "U5") (pin "R15") (pinfunction "USB_DEV_HS_P/PB15_R15") (pintype "passive"))
    )
    (net (code "16") (name "/STLK_VCP_RX") (class "Default")
      (node (ref "R48") (pin "1") (pinfunction "1_1") (pintype "passive"))
      (node (ref "U5") (pin "C10") (pinfunction "STLK_VCP_RX/PG9_C10") (pintype "passive"))
    )
    (net (code "17") (name "/STLK_VCP_TX") (class "Default")
      (node (ref "R49") (pin "1") (pinfunction "1_1") (pintype "passive"))
      (node (ref "U5") (pin "A7") (pinfunction "STLK_VCP_TX/PG14_A7") (pintype "passive"))
    )
    (net (code "18") (name "/T_JTDI") (class "Default")
      (node (ref "CN4") (pin "10") (pinfunction "10_10") (pintype "passive"))
      (node (ref "R47") (pin "2") (pinfunction "2_2") (pintype "passive"))
      (node (ref "U6") (pin "4") (pinfunction "IO3_4") (pintype "passive"))
    )
    (net (code "19") (name "/T_NRST") (class "Default")
      (node (ref "CN4") (pin "12") (pinfunction "12_12") (pintype "passive"))
      (node (ref "R50") (pin "2") (pinfunction "2_2") (pintype "passive"))
      (node (ref "U1") (pin "5") (pinfunction "IO4_5") (pintype "passive"))
    )
    (net (code "20") (name "/T_PWR_EN") (class "Default")
      (node (ref "R8") (pin "2") (pinfunction "2_2") (pintype "passive"))
      (node (ref "U19") (pin "2") (pinfunction "EN/UVLO_2") (pintype "passive"))
      (node (ref "U4") (pin "4") (pinfunction "EN_4") (pintype "passive"))
      (node (ref "U5") (pin "R5") (pinfunction "T_PWR_EN/PB0_R5") (pintype "passive"))
    )
    (net (code "21") (name "/T_PWR_EXT") (class "Default")
      (node (ref "R11") (pin "1") (pinfunction "1_1") (pintype "passive"))
      (node (ref "R12") (pin "1") (pinfunction "1_1") (pintype "passive"))
      (node (ref "U5") (pin "R4") (pinfunction "T_PWR_EXT/PB1_R4") (pintype "passive"))
    )
    (net (code "22") (name "/T_PWR_INT") (class "Default")
      (node (ref "R18") (pin "2") (pinfunction "2_2") (pintype "passive"))
      (node (ref "R51") (pin "2") (pinfunction "2_2") (pintype "passive"))
      (node (ref "U5") (pin "B13") (pinfunction "T_PWR_INT/PC11_B13") (pintype "passive"))
    )
    (net (code "23") (name "/T_PWR_LED") (class "Default")
      (node (ref "R23") (pin "2") (pinfunction "2_2") (pintype "passive"))
      (node (ref "R24") (pin "2") (pinfunction "2_2") (pintype "passive"))
      (node (ref "U5") (pin "H15") (pinfunction "T_PWR_LED/PC6_H15") (pintype "passive"))
    )
    (net (code "24") (name "/T_PWR_SEL1") (class "Default")
      (node (ref "R20") (pin "2") (pinfunction "2_2") (pintype "passive"))
      (node (ref "U5") (pin "D10") (pinfunction "T_PWR_SEL1/PD4_D10") (pintype "passive"))
    )
    (net (code "25") (name "/T_PWR_SEL2") (class "Default")
      (node (ref "R21") (pin "2") (pinfunction "2_2") (pintype "passive"))
      (node (ref "U5") (pin "C11") (pinfunction "T_PWR_SEL2/PD5_C11") (pintype "passive"))
    )
    (net (code "26") (name "/T_SWCLK") (class "Default")
      (node (ref "CN4") (pin "6") (pinfunction "6_6") (pintype "passive"))
      (node (ref "R44") (pin "2") (pinfunction "2_2") (pintype "passive"))
      (node (ref "U6") (pin "1") (pinfunction "IO1_1") (pintype "passive"))
    )
    (net (code "27") (name "/T_SWDIO") (class "Default")
      (node (ref "CN4") (pin "4") (pinfunction "4_4") (pintype "passive"))
      (node (ref "R45") (pin "2") (pinfunction "2_2") (pintype "passive"))
      (node (ref "U6") (pin "5") (pinfunction "IO4_5") (pintype "passive"))
    )
    (net (code "28") (name "/T_SWO") (class "Default")
      (node (ref "CN4") (pin "8") (pinfunction "8_8") (pintype "passive"))
      (node (ref "R46") (pin "2") (pinfunction "2_2") (pintype "passive"))
      (node (ref "U6") (pin "3") (pinfunction "IO2_3") (pintype "passive"))
    )
    (net (code "29") (name "/T_VCC_AIN") (class "Default")
      (node (ref "R16") (pin "1") (pinfunction "1_1") (pintype "passive"))
      (node (ref "R19") (pin "1") (pinfunction "1_1") (pintype "passive"))
      (node (ref "U5") (pin "N3") (pinfunction "T_VCC_AIN/PA0_N3") (pintype "passive"))
    )
    (net (code "30") (name "/T_VCP_RX") (class "Default")
      (node (ref "CN4") (pin "13") (pinfunction "13_13") (pintype "passive"))
      (node (ref "R49") (pin "2") (pinfunction "2_2") (pintype "passive"))
      (node (ref "U1") (pin "3") (pinfunction "IO2_3") (pintype "passive"))
    )
    (net (code "31") (name "/T_VCP_TX") (class "Default")
      (node (ref "CN4") (pin "14") (pinfunction "14_14") (pintype "passive"))
      (node (ref "R48") (pin "2") (pinfunction "2_2") (pintype "passive"))
      (node (ref "U1") (pin "1") (pinfunction "IO1_1") (pintype "passive"))
    )
    (net (code "32") (name "3V3") (class "Default")
      (node (ref "CN4") (pin "3") (pinfunction "3_3") (pintype "passive"))
      (node (ref "R19") (pin "2") (pinfunction "2_2") (pintype "passive"))
    )
    (net (code "33") (name "3V3_STLK") (class "Default")
      (node (ref "C13") (pin "1") (pinfunction "1_1") (pintype "passive"))
      (node (ref "C14") (pin "1") (pinfunction "1_1") (pintype "passive"))
      (node (ref "C15") (pin "1") (pinfunction "1_1") (pintype "passive"))
      (node (ref "C16") (pin "1") (pinfunction "1_1") (pintype "passive"))
      (node (ref "C17") (pin "1") (pinfunction "1_1") (pintype "passive"))
      (node (ref "C18") (pin "1") (pinfunction "1_1") (pintype "passive"))
      (node (ref "C21") (pin "1") (pinfunction "1_1") (pintype "passive"))
      (node (ref "C22") (pin "1") (pinfunction "1_1") (pintype "passive"))
      (node (ref "C23") (pin "1") (pinfunction "1_1") (pintype "passive"))
      (node (ref "C24") (pin "1") (pinfunction "1_1") (pintype "passive"))
      (node (ref "C25") (pin "1") (pinfunction "1_1") (pintype "passive"))
      (node (ref "C26") (pin "1") (pinfunction "1_1") (pintype "passive"))
      (node (ref "C27") (pin "1") (pinfunction "1_1") (pintype "passive"))
      (node (ref "C31") (pin "2") (pinfunction "2_2") (pintype "passive"))
      (node (ref "C6") (pin "1") (pinfunction "1_1") (pintype "passive"))
      (node (ref "C7") (pin "1") (pinfunction "1_1") (pintype "passive"))
      (node (ref "C8") (pin "1") (pinfunction "1_1") (pintype "passive"))
      (node (ref "C9") (pin "1") (pinfunction "1_1") (pintype "passive"))
      (node (ref "CN2") (pin "1") (pinfunction "1_1") (pintype "passive"))
      (node (ref "LD1") (pin "4") (pinfunction "Green_anode_4") (pintype "passive"))
      (node (ref "LD7") (pin "4") (pinfunction "Green_anode_4") (pintype "passive"))
      (node (ref "R10") (pin "2") (pinfunction "2_2") (pintype "passive"))
      (node (ref "U5") (pin "C1") (pinfunction "VBAT_C1") (pintype "passive"))
      (node (ref "U5") (pin "C5") (pinfunction "VDD_C5") (pintype "passive"))
      (node (ref "U5") (pin "C6") (pinfunction "PDR_ON_C6") (pintype "passive"))
      (node (ref "U5") (pin "C7") (pinfunction "VDD_C7") (pintype "passive"))
      (node (ref "U5") (pin "C8") (pinfunction "VDD_C8") (pintype "passive"))
      (node (ref "U5") (pin "C9") (pinfunction "VDD_C9") (pintype "passive"))
      (node (ref "U5") (pin "F3") (pinfunction "VDD_F3") (pintype "passive"))
      (node (ref "U5") (pin "G13") (pinfunction "VDD_G13") (pintype "passive"))
      (node (ref "U5") (pin "G3") (pinfunction "VDD_G3") (pintype "passive"))
      (node (ref "U5") (pin "H13") (pinfunction "VDD_H13") (pintype "passive"))
      (node (ref "U5") (pin "J12") (pinfunction "VDD_J12") (pintype "passive"))
      (node (ref "U5") (pin "J13") (pinfunction "VDD_J13") (pintype "passive"))
      (node (ref "U5") (pin "K4") (pinfunction "VDD_K4") (pintype "passive"))
      (node (ref "U5") (pin "N10") (pinfunction "VDD_N10") (pintype "passive"))
      (node (ref "U5") (pin "N8") (pinfunction "VDD_N8") (pintype "passive"))
      (node (ref "U5") (pin "N9") (pinfunction "VDD_N9") (pintype "passive"))
      (node (ref "U5") (pin "P1") (pinfunction "VREF+_P1") (pintype "passive"))
      (node (ref "U5") (pin "R1") (pinfunction "VDDA_R1") (pintype "passive"))
      (node (ref "U7") (pin "1") (pinfunction "VOUT_1") (pintype "passive"))
    )
    (net (code "34") (name "5V") (class "Default")
      (node (ref "R11") (pin "2") (pinfunction "2_2") (pintype "passive"))
    )
    (net (code "35") (name "5V_STLK") (class "Default")
      (node (ref "C28") (pin "2") (pinfunction "2_2") (pintype "passive"))
      (node (ref "C5") (pin "2") (pinfunction "2_2") (pintype "passive"))
      (node (ref "U19") (pin "5") (pinfunction "OUT_5") (pintype "passive"))
      (node (ref "U4") (pin "1") (pinfunction "OUT_1") (pintype "passive"))
    )
    (net (code "36") (name "5V_VIN") (class "Default")
      (node (ref "D2") (pin "1") (pinfunction "A_1") (pintype "passive"))
    )
    (net (code "37") (name "E5V") (class "Default")
      (node (ref "D4") (pin "1") (pinfunction "A_1") (pintype "passive"))
    )
    (net (code "38") (name "GND") (class "Default")
      (node (ref "C1") (pin "1") (pinfunction "1_1") (pintype "passive"))
      (node (ref "C10") (pin "1") (pinfunction "1_1") (pintype "passive"))
      (node (ref "C11") (pin "1") (pinfunction "1_1") (pintype "passive"))
      (node (ref "C12") (pin "1") (pinfunction "1_1") (pintype "passive"))
      (node (ref "C13") (pin "2") (pinfunction "2_2") (pintype "passive"))
      (node (ref "C14") (pin "2") (pinfunction "2_2") (pintype "passive"))
      (node (ref "C15") (pin "2") (pinfunction "2_2") (pintype "passive"))
      (node (ref "C16") (pin "2") (pinfunction "2_2") (pintype "passive"))
      (node (ref "C17") (pin "2") (pinfunction "2_2") (pintype "passive"))
      (node (ref "C18") (pin "2") (pinfunction "2_2") (pintype "passive"))
      (node (ref "C19") (pin "1") (pinfunction "1_1") (pintype "passive"))
      (node (ref "C2") (pin "2") (pinfunction "2_2") (pintype "passive"))
      (node (ref "C20") (pin "2") (pinfunction "2_2") (pintype "passive"))
      (node (ref "C21") (pin "2") (pinfunction "2_2") (pintype "passive"))
      (node (ref "C22") (pin "2") (pinfunction "2_2") (pintype "passive"))
      (node (ref "C23") (pin "2") (pinfunction "2_2") (pintype "passive"))
      (node (ref "C24") (pin "2") (pinfunction "2_2") (pintype "passive"))
      (node (ref "C25") (pin "2") (pinfunction "2_2") (pintype "passive"))
      (node (ref "C26") (pin "2") (pinfunction "2_2") (pintype "passive"))
      (node (ref "C27") (pin "2") (pinfunction "2_2") (pintype "passive"))
      (node (ref "C28") (pin "1") (pinfunction "1_1") (pintype "passive"))
      (node (ref "C29") (pin "1") (pinfunction "1_1") (pintype "passive"))
      (node (ref "C3") (pin "2") (pinfunction "2_2") (pintype "passive"))
      (node (ref "C30") (pin "1") (pinfunction "1_1") (pintype "passive"))
      (node (ref "C31") (pin "1") (pinfunction "1_1") (pintype "passive"))
      (node (ref "C32") (pin "1") (pinfunction "1_1") (pintype "passive"))
      (node (ref "C33") (pin "1") (pinfunction "1_1") (pintype "passive"))
      (node (ref "C4") (pin "1") (pinfunction "1_1") (pintype "passive"))
      (node (ref "C46") (pin "1") (pinfunction "1_1") (pintype "passive"))
      (node (ref "C5") (pin "1") (pinfunction "1_1") (pintype "passive"))
      (node (ref "C6") (pin "2") (pinfunction "2_2") (pintype "passive"))
      (node (ref "C7") (pin "2") (pinfunction "2_2") (pintype "passive"))
      (node (ref "C8") (pin "2") (pinfunction "2_2") (pintype "passive"))
      (node (ref "C9") (pin "2") (pinfunction "2_2") (pintype "passive"))
      (node (ref "CN1") (pin "A1") (pinfunction "GND1_A1") (pintype "passive"))
      (node (ref "CN1") (pin "A12") (pinfunction "GND2_A12") (pintype "passive"))
      (node (ref "CN1") (pin "B1") (pinfunction "GND3_B1") (pintype "passive"))
      (node (ref "CN1") (pin "B12") (pinfunction "GND4_B12") (pintype "passive"))
      (node (ref "CN1") (pin "SH1") (pinfunction "Shield1_SH1") (pintype "passive"))
      (node (ref "CN1") (pin "SH2") (pinfunction "Shield2_SH2") (pintype "passive"))
      (node (ref "CN1") (pin "SH3") (pinfunction "Shield3_SH3") (pintype "passive"))
      (node (ref "CN1") (pin "SH4") (pinfunction "Shield4_SH4") (pintype "passive"))
      (node (ref "CN2") (pin "3") (pinfunction "3_3") (pintype "passive"))
      (node (ref "CN4") (pin "5") (pinfunction "5_5") (pintype "passive"))
      (node (ref "CN4") (pin "7") (pinfunction "7_7") (pintype "passive"))
      (node (ref "JP1") (pin "2") (pinfunction "NO_2") (pintype "passive"))
      (node (ref "LD1") (pin "3") (pinfunction "RED_cathode_3") (pintype "passive"))
      (node (ref "LD7") (pin "3") (pinfunction "RED_cathode_3") (pintype "passive"))
      (node (ref "R12") (pin "2") (pinfunction "2_2") (pintype "passive"))
      (node (ref "R15") (pin "1") (pinfunction "1_1") (pintype "passive"))
      (node (ref "R16") (pin "2") (pinfunction "2_2") (pintype "passive"))
      (node (ref "R17") (pin "2") (pinfunction "2_2") (pintype "passive"))
      (node (ref "R18") (pin "1") (pinfunction "1_1") (pintype "passive"))
      (node (ref "R22") (pin "2") (pinfunction "2_2") (pintype "passive"))
      (node (ref "R5") (pin "2") (pinfunction "2_2") (pintype "passive"))
      (node (ref "R8") (pin "1") (pinfunction "1_1") (pintype "passive"))
      (node (ref "R9") (pin "2") (pinfunction "2_2") (pintype "passive"))
      (node (ref "U1") (pin "2") (pinfunction "GND_2") (pintype "passive"))
      (node (ref "U19") (pin "8") (pinfunction "GND_8") (pintype "passive"))
      (node (ref "U19") (pin "9") (pinfunction "EP_9") (pintype "passive"))
      (node (ref "U2") (pin "3") (pinfunction "GND_3") (pintype "passive"))
      (node (ref "U3") (pin "2") (pinfunction "GND_2") (pintype "passive"))
      (node (ref "U4") (pin "2") (pinfunction "GND_2") (pintype "passive"))
      (node (ref "U5") (pin "D5") (pinfunction "VSS_D5") (pintype "passive"))
      (node (ref "U5") (pin "D6") (pinfunction "BOOT0_D6") (pintype "passive"))
      (node (ref "U5") (pin "D7") (pinfunction "VSS_D7") (pintype "passive"))
      (node (ref "U5") (pin "D8") (pinfunction "VSS_D8") (pintype "passive"))
      (node (ref "U5") (pin "D9") (pinfunction "VSS_D9") (pintype "passive"))
      (node (ref "U5") (pin "F10") (pinfunction "VSS_F10") (pintype "passive"))
      (node (ref "U5") (pin "F12") (pinfunction "VSS_F12") (pintype "passive"))
      (node (ref "U5") (pin "F2") (pinfunction "VSS_F2") (pintype "passive"))
      (node (ref "U5") (pin "F6") (pinfunction "VSS_F6") (pintype "passive"))
      (node (ref "U5") (pin "F7") (pinfunction "VSS_F7") (pintype "passive"))
      (node (ref "U5") (pin "F8") (pinfunction "VSS_F8") (pintype "passive"))
      (node (ref "U5") (pin "F9") (pinfunction "VSS_F9") (pintype "passive"))
      (node (ref "U5") (pin "G10") (pinfunction "VSS_G10") (pintype "passive"))
      (node (ref "U5") (pin "G12") (pinfunction "VSS_G12") (pintype "passive"))
      (node (ref "U5") (pin "G2") (pinfunction "VSS_G2") (pintype "passive"))
      (node (ref "U5") (pin "G6") (pinfunction "VSS_G6") (pintype "passive"))
      (node (ref "U5") (pin "G7") (pinfunction "VSS_G7") (pintype "passive"))
      (node (ref "U5") (pin "G8") (pinfunction "VSS_G8") (pintype "passive"))
      (node (ref "U5") (pin "G9") (pinfunction "VSS_G9") (pintype "passive"))
      (node (ref "U5") (pin "H10") (pinfunction "VSS_H10") (pintype "passive"))
      (node (ref "U5") (pin "H12") (pinfunction "VSS_H12") (pintype "passive"))
      (node (ref "U5") (pin "H6") (pinfunction "VSS_H6") (pintype "passive"))
      (node (ref "U5") (pin "H7") (pinfunction "VSS_H7") (pintype "passive"))
      (node (ref "U5") (pin "H8") (pinfunction "VSS_H8") (pintype "passive"))
      (node (ref "U5") (pin "H9") (pinfunction "VSS_H9") (pintype "passive"))
      (node (ref "U5") (pin "J10") (pinfunction "VSS_J10") (pintype "passive"))
      (node (ref "U5") (pin "J6") (pinfunction "VSS_J6") (pintype "passive"))
      (node (ref "U5") (pin "J7") (pinfunction "VSS_J7") (pintype "passive"))
      (node (ref "U5") (pin "J8") (pinfunction "VSS_J8") (pintype "passive"))
      (node (ref "U5") (pin "J9") (pinfunction "VSS_J9") (pintype "passive"))
      (node (ref "U5") (pin "K10") (pinfunction "VSS_K10") (pintype "passive"))
      (node (ref "U5") (pin "K6") (pinfunction "VSS_K6") (pintype "passive"))
      (node (ref "U5") (pin "K7") (pinfunction "VSS_K7") (pintype "passive"))
      (node (ref "U5") (pin "K8") (pinfunction "VSS_K8") (pintype "passive"))
      (node (ref "U5") (pin "K9") (pinfunction "VSS_K9") (pintype "passive"))
      (node (ref "U5") (pin "L4") (pinfunction "BYPASS-REG_L4") (pintype "passive"))
      (node (ref "U5") (pin "M1") (pinfunction "VSSA_M1") (pintype "passive"))
      (node (ref "U5") (pin "M8") (pinfunction "VSS_M8") (pintype "passive"))
      (node (ref "U5") (pin "M9") (pinfunction "VSS_M9") (pintype "passive"))
      (node (ref "U5") (pin "N1") (pinfunction "VREF-_N1") (pintype "passive"))
      (node (ref "U6") (pin "2") (pinfunction "GND_2") (pintype "passive"))
      (node (ref "U7") (pin "2") (pinfunction "GND_2") (pintype "passive"))
      (node (ref "X1") (pin "2") (pinfunction "2_2") (pintype "passive"))
      (node (ref "X1") (pin "4") (pinfunction "4_4") (pintype "passive"))
    )
    (net (code "39") (name "Net-(CN1-CC1)") (class "Default")
      (node (ref "CN1") (pin "A5") (pinfunction "CC1_A5") (pintype "passive"))
      (node (ref "R13") (pin "1") (pinfunction "1_1") (pintype "passive"))
      (node (ref "R9") (pin "1") (pinfunction "1_1") (pintype "passive"))
    )
    (net (code "40") (name "Net-(CN1-CC2)") (class "Default")
      (node (ref "CN1") (pin "B5") (pinfunction "CC2_B5") (pintype "passive"))
      (node (ref "R14") (pin "1") (pinfunction "1_1") (pintype "passive"))
      (node (ref "R17") (pin "1") (pinfunction "1_1") (pintype "passive"))
    )
    (net (code "41") (name "Net-(D1-K)") (class "Default")
      (node (ref "C19") (pin "2") (pinfunction "2_2") (pintype "passive"))
      (node (ref "D1") (pin "2") (pinfunction "K_2") (pintype "passive"))
      (node (ref "D2") (pin "2") (pinfunction "K_2") (pintype "passive"))
      (node (ref "D3") (pin "2") (pinfunction "K_2") (pintype "passive"))
      (node (ref "D4") (pin "2") (pinfunction "K_2") (pintype "passive"))
      (node (ref "U7") (pin "3") (pinfunction "VIN_3") (pintype "passive"))
      (node (ref "U7") (pin "5") (pinfunction "EN_5") (pintype "passive"))
    )
    (net (code "42") (name "Net-(LD1-Green_cathode)") (class "Default")
      (node (ref "LD1") (pin "2") (pinfunction "Green_cathode_2") (pintype "passive"))
      (node (ref "R2") (pin "2") (pinfunction "2_2") (pintype "passive"))
    )
    (net (code "43") (name "Net-(LD1-Red_anode)") (class "Default")
      (node (ref "LD1") (pin "1") (pinfunction "Red_anode_1") (pintype "passive"))
      (node (ref "R3") (pin "1") (pinfunction "1_1") (pintype "passive"))
    )
    (net (code "44") (name "Net-(LD4-Pad1)") (class "Default")
      (node (ref "LD4") (pin "1") (pintype "passive"))
      (node (ref "R1") (pin "1") (pinfunction "1_1") (pintype "passive"))
    )
    (net (code "45") (name "Net-(LD7-Green_cathode)") (class "Default")
      (node (ref "LD7") (pin "2") (pinfunction "Green_cathode_2") (pintype "passive"))
      (node (ref "R24") (pin "1") (pinfunction "1_1") (pintype "passive"))
    )
    (net (code "46") (name "Net-(LD7-Red_anode)") (class "Default")
      (node (ref "LD7") (pin "1") (pinfunction "Red_anode_1") (pintype "passive"))
      (node (ref "R23") (pin "1") (pinfunction "1_1") (pintype "passive"))
    )
    (net (code "47") (name "Net-(U4-~{FAULT})") (class "Default")
      (node (ref "LD4") (pin "2") (pintype "passive"))
      (node (ref "R6") (pin "1") (pinfunction "1_1") (pintype "passive"))
      (node (ref "U4") (pin "3") (pinfunction "~{FAULT}_3") (pintype "passive"))
    )
    (net (code "48") (name "Net-(U5A-HW_TYP_0{slash}PI4)") (class "Default")
      (node (ref "R10") (pin "1") (pinfunction "1_1") (pintype "passive"))
      (node (ref "U5") (pin "D4") (pinfunction "HW_TYP_0/PI4_D4") (pintype "passive"))
    )
    (net (code "49") (name "Net-(U5A-REXT_OTGPHY)") (class "Default")
      (node (ref "R5") (pin "1") (pinfunction "1_1") (pintype "passive"))
      (node (ref "U5") (pin "J15") (pinfunction "REXT_OTGPHY_J15") (pintype "passive"))
    )
    (net (code "50") (name "Net-(U5A-T_JCLK_OUT{slash}PB2)") (class "Default")
      (node (ref "R44") (pin "1") (pinfunction "1_1") (pintype "passive"))
      (node (ref "U5") (pin "A10") (pinfunction "T_JRCLK/PB3_A10") (pintype "passive"))
      (node (ref "U5") (pin "M11") (pinfunction "T_SWCLK/PH6_M11") (pintype "passive"))
      (node (ref "U5") (pin "M6") (pinfunction "T_JCLK_OUT/PB2_M6") (pintype "passive"))
    )
    (net (code "51") (name "Net-(U5A-T_JTDO{slash}PB5)") (class "Default")
      (node (ref "R46") (pin "1") (pinfunction "1_1") (pintype "passive"))
      (node (ref "U5") (pin "A6") (pinfunction "T_JTDO/PB5_A6") (pintype "passive"))
      (node (ref "U5") (pin "D12") (pinfunction "T_SWO/PD2_D12") (pintype "passive"))
    )
    (net (code "52") (name "Net-(U5A-T_JTMS{slash}T_SWDIO_OUT{slash}PF9)") (class "Default")
      (node (ref "R45") (pin "1") (pinfunction "1_1") (pintype "passive"))
      (node (ref "U5") (pin "L2") (pinfunction "T_JTMS/T_SWDIO_OUT/PF9_L2") (pintype "passive"))
      (node (ref "U5") (pin "N12") (pinfunction "T_SWDIO_IN/PH7_N12") (pintype "passive"))
    )
    (net (code "53") (name "Net-(U5A-T_MCO{slash}PA8)") (class "Default")
      (node (ref "R4") (pin "1") (pinfunction "1_1") (pintype "passive"))
      (node (ref "U5") (pin "F15") (pinfunction "T_MCO/PA8_F15") (pintype "passive"))
    )
    (net (code "54") (name "Net-(U5A-T_NRST{slash}PA6)") (class "Default")
      (node (ref "R50") (pin "1") (pinfunction "1_1") (pintype "passive"))
      (node (ref "U5") (pin "P3") (pinfunction "T_NRST/PA6_P3") (pintype "passive"))
    )
    (net (code "55") (name "Net-(U5A-V12_OTGPHY)") (class "Default")
      (node (ref "C4") (pin "2") (pinfunction "2_2") (pintype "passive"))
      (node (ref "U5") (pin "J14") (pinfunction "V12_OTGPHY_J14") (pintype "passive"))
    )
    (net (code "56") (name "Net-(U5B-VCAP1)") (class "Default")
      (node (ref "C12") (pin "2") (pinfunction "2_2") (pintype "passive"))
      (node (ref "U5") (pin "M10") (pinfunction "VCAP1_M10") (pintype "passive"))
    )
    (net (code "57") (name "Net-(U5B-VCAP2)") (class "Default")
      (node (ref "C10") (pin "2") (pinfunction "2_2") (pintype "passive"))
      (node (ref "U5") (pin "F13") (pinfunction "VCAP2_F13") (pintype "passive"))
    )
    (net (code "58") (name "Net-(U19-ILM)") (class "Default")
      (node (ref "R20") (pin "1") (pinfunction "1_1") (pintype "passive"))
      (node (ref "R21") (pin "1") (pinfunction "1_1") (pintype "passive"))
      (node (ref "R22") (pin "1") (pinfunction "1_1") (pintype "passive"))
      (node (ref "U19") (pin "7") (pinfunction "ILM_7") (pintype "passive"))
    )
    (net (code "59") (name "Net-(U19-QOD)") (class "Default")
      (node (ref "R51") (pin "1") (pinfunction "1_1") (pintype "passive"))
      (node (ref "U19") (pin "6") (pinfunction "QOD_6") (pintype "passive"))
    )
    (net (code "60") (name "Net-(U19-dVdt)") (class "Default")
      (node (ref "C30") (pin "2") (pinfunction "2_2") (pintype "passive"))
      (node (ref "U19") (pin "1") (pinfunction "dVdt_1") (pintype "passive"))
    )
    (net (code "61") (name "VBUS_STLK") (class "Default")
      (node (ref "C11") (pin "2") (pinfunction "2_2") (pintype "passive"))
      (node (ref "C2") (pin "1") (pinfunction "1_1") (pintype "passive"))
      (node (ref "C29") (pin "2") (pinfunction "2_2") (pintype "passive"))
      (node (ref "CN1") (pin "A4") (pinfunction "VBUS1_A4") (pintype "passive"))
      (node (ref "CN1") (pin "A9") (pinfunction "VBUS2_A9") (pintype "passive"))
      (node (ref "CN1") (pin "B4") (pinfunction "VBUS3_B4") (pintype "passive"))
      (node (ref "CN1") (pin "B9") (pinfunction "VBUS4_B9") (pintype "passive"))
      (node (ref "D1") (pin "1") (pinfunction "A_1") (pintype "passive"))
      (node (ref "R1") (pin "2") (pinfunction "2_2") (pintype "passive"))
      (node (ref "R6") (pin "2") (pinfunction "2_2") (pintype "passive"))
      (node (ref "U19") (pin "3") (pinfunction "IN_3") (pintype "passive"))
      (node (ref "U19") (pin "4") (pinfunction "IN_4") (pintype "passive"))
      (node (ref "U3") (pin "1") (pinfunction "IO1_1") (pintype "passive"))
      (node (ref "U4") (pin "5") (pinfunction "IN_5") (pintype "passive"))
    )
    (net (code "62") (name "VBUSc") (class "Default")
      (node (ref "D3") (pin "1") (pinfunction "A_1") (pintype "passive"))
    )
    (net (code "63") (name "unconnected-(CN1-RX1+-PadB11)") (class "Default")
      (node (ref "CN1") (pin "B11") (pinfunction "RX1+_B11") (pintype "passive+no_connect"))
    )
    (net (code "64") (name "unconnected-(CN1-RX1--PadB10)") (class "Default")
      (node (ref "CN1") (pin "B10") (pinfunction "RX1-_B10") (pintype "passive+no_connect"))
    )
    (net (code "65") (name "unconnected-(CN1-RX2+-PadA11)") (class "Default")
      (node (ref "CN1") (pin "A11") (pinfunction "RX2+_A11") (pintype "passive+no_connect"))
    )
    (net (code "66") (name "unconnected-(CN1-RX2--PadA10)") (class "Default")
      (node (ref "CN1") (pin "A10") (pinfunction "RX2-_A10") (pintype "passive+no_connect"))
    )
    (net (code "67") (name "unconnected-(CN1-SBU1-PadA8)") (class "Default")
      (node (ref "CN1") (pin "A8") (pinfunction "SBU1_A8") (pintype "passive+no_connect"))
    )
    (net (code "68") (name "unconnected-(CN1-SBU2-PadB8)") (class "Default")
      (node (ref "CN1") (pin "B8") (pinfunction "SBU2_B8") (pintype "passive+no_connect"))
    )
    (net (code "69") (name "unconnected-(CN1-TX1+-PadA2)") (class "Default")
      (node (ref "CN1") (pin "A2") (pinfunction "TX1+_A2") (pintype "passive+no_connect"))
    )
    (net (code "70") (name "unconnected-(CN1-TX1--PadA3)") (class "Default")
      (node (ref "CN1") (pin "A3") (pinfunction "TX1-_A3") (pintype "passive+no_connect"))
    )
    (net (code "71") (name "unconnected-(CN1-TX2+-PadB2)") (class "Default")
      (node (ref "CN1") (pin "B2") (pinfunction "TX2+_B2") (pintype "passive+no_connect"))
    )
    (net (code "72") (name "unconnected-(CN1-TX2--PadB3)") (class "Default")
      (node (ref "CN1") (pin "B3") (pinfunction "TX2-_B3") (pintype "passive+no_connect"))
    )
    (net (code "73") (name "unconnected-(CN4-Pad1)") (class "Default")
      (node (ref "CN4") (pin "1") (pinfunction "1_1") (pintype "passive+no_connect"))
    )
    (net (code "74") (name "unconnected-(CN4-Pad2)") (class "Default")
      (node (ref "CN4") (pin "2") (pinfunction "2_2") (pintype "passive+no_connect"))
    )
    (net (code "75") (name "unconnected-(CN4-Pad9)") (class "Default")
      (node (ref "CN4") (pin "9") (pinfunction "9_9") (pintype "passive+no_connect"))
    )
    (net (code "76") (name "unconnected-(U1-IO3-Pad4)") (class "Default")
      (node (ref "U1") (pin "4") (pinfunction "IO3_4") (pintype "passive+no_connect"))
    )
    (net (code "77") (name "unconnected-(U2-NC-Pad4)") (class "Default")
      (node (ref "U2") (pin "4") (pinfunction "NC_4") (pintype "passive+no_connect"))
    )
    (net (code "78") (name "unconnected-(U5A-GNDDetect{slash}PG5-PadK13)") (class "Default")
      (node (ref "U5") (pin "K13") (pinfunction "GNDDetect/PG5_K13") (pintype "passive+no_connect"))
    )
    (net (code "79") (name "unconnected-(U5A-HW_TYP_1{slash}PI5-PadC4)") (class "Default")
      (node (ref "U5") (pin "C4") (pinfunction "HW_TYP_1/PI5_C4") (pintype "passive+no_connect"))
    )
    (net (code "80") (name "unconnected-(U5A-T_JNRST{slash}PF13-PadN6)") (class "Default")
      (node (ref "U5") (pin "N6") (pinfunction "T_JNRST/PF13_N6") (pintype "passive+no_connect"))
    )
    (net (code "81") (name "unconnected-(U5A-T_SW_DIR{slash}PA7-PadR3)") (class "Default")
      (node (ref "U5") (pin "R3") (pinfunction "T_SW_DIR/PA7_R3") (pintype "passive+no_connect"))
    )
    (net (code "82") (name "unconnected-(U7-NC{slash}ADJ-Pad4)") (class "Default")
      (node (ref "U7") (pin "4") (pinfunction "NC/ADJ_4") (pintype "passive+no_connect"))
    )
  )
)
